# VOLTAGE_MEASURE_DC_V2.net
KiCad netlist of a schematic drawn in Altium Designer
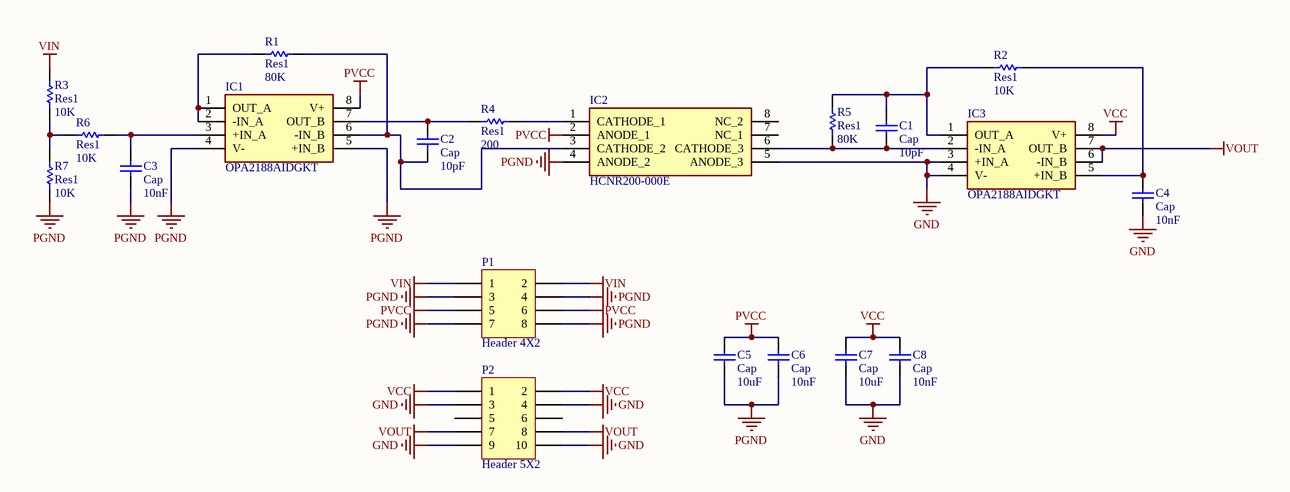
[diagram p0: VOLTAGE_MEASURE_DC_V2.SchDoc]

(export (version "E")
  (design (tool "Eeschema 10.0.6"))
  (components
    (comp (ref "C1")
      (value "Cap")
      (footprint "1608[0603]")
      (description "Capacitor")
      (fields (field (name "ALTIUM_VALUE") "10pF") (field (name "PUBLISHER") "Altium Limited"))
      (libsource (lib "Miscellaneous Devices") (part "Cap"))
    )
    (comp (ref "C2")
      (value "Cap")
      (footprint "1608[0603]")
      (description "Capacitor")
      (fields (field (name "ALTIUM_VALUE") "10pF") (field (name "PUBLISHER") "Altium Limited"))
      (libsource (lib "Miscellaneous Devices") (part "Cap"))
    )
    (comp (ref "C3")
      (value "Cap")
      (footprint "1608[0603]")
      (description "Capacitor")
      (fields (field (name "ALTIUM_VALUE") "10nF") (field (name "PUBLISHER") "Altium Limited"))
      (libsource (lib "Miscellaneous Devices") (part "Cap"))
    )
    (comp (ref "C4")
      (value "Cap")
      (footprint "1608[0603]")
      (description "Capacitor")
      (fields (field (name "ALTIUM_VALUE") "10nF") (field (name "PUBLISHER") "Altium Limited"))
      (libsource (lib "Miscellaneous Devices") (part "Cap"))
    )
    (comp (ref "C5")
      (value "Cap")
      (footprint "1608[0603]")
      (description "Capacitor")
      (fields (field (name "ALTIUM_VALUE") "10uF") (field (name "PUBLISHER") "Altium Limited"))
      (libsource (lib "Miscellaneous Devices") (part "Cap"))
    )
    (comp (ref "C6")
      (value "Cap")
      (footprint "1608[0603]")
      (description "Capacitor")
      (fields (field (name "ALTIUM_VALUE") "10nF") (field (name "PUBLISHER") "Altium Limited"))
      (libsource (lib "Miscellaneous Devices") (part "Cap"))
    )
    (comp (ref "C7")
      (value "Cap")
      (footprint "1608[0603]")
      (description "Capacitor")
      (fields (field (name "ALTIUM_VALUE") "10uF") (field (name "PUBLISHER") "Altium Limited"))
      (libsource (lib "Miscellaneous Devices") (part "Cap"))
    )
    (comp (ref "C8")
      (value "Cap")
      (footprint "1608[0603]")
      (description "Capacitor")
      (fields (field (name "ALTIUM_VALUE") "10nF") (field (name "PUBLISHER") "Altium Limited"))
      (libsource (lib "Miscellaneous Devices") (part "Cap"))
    )
    (comp (ref "IC1")
      (value "OPA2188AIDGKT")
      (footprint "SamacSys:SOP65P490X110-8N")
      (description "Integrated Circuit")
      (fields
        (field (name "MOUSER PART NUMBER") "595-OPA2188AIDGKT")
        (field (name "RS PART NUMBER") "8122561P")
      )
      (libsource (lib "*") (part "OPA2188AIDGKT"))
    )
    (comp (ref "IC2")
      (value "HCNR200-000E")
      (footprint "SamacSys:DIP1100W56P254L1115H510Q8N")
      (description "Integrated Circuit")
      (fields
        (field (name "MOUSER PART NUMBER") "630-HCNR200-000E")
        (field (name "RS PART NUMBER") "6961248P")
      )
      (libsource (lib "*") (part "HCNR200-000E"))
    )
    (comp (ref "IC3")
      (value "OPA2188AIDGKT")
      (footprint "SamacSys:SOP65P490X110-8N")
      (description "Integrated Circuit")
      (fields
        (field (name "MOUSER PART NUMBER") "595-OPA2188AIDGKT")
        (field (name "RS PART NUMBER") "8122561P")
      )
      (libsource (lib "*") (part "OPA2188AIDGKT"))
    )
    (comp (ref "P1")
      (value "Header 4X2")
      (footprint "HDR2X4")
      (description "Header, 4-Pin, Dual row")
      (fields (field (name "PUBLISHER") "Altium Limited"))
      (libsource (lib "Miscellaneous Connectors") (part "Header 4X2"))
    )
    (comp (ref "P2")
      (value "Header 5X2")
      (footprint "HDR2X5")
      (description "Header, 5-Pin, Dual row")
      (fields (field (name "PUBLISHER") "Altium Limited"))
      (libsource (lib "Miscellaneous Connectors") (part "Header 5X2"))
    )
    (comp (ref "R1")
      (value "Res1")
      (footprint "J1-0603")
      (description "Resistor")
      (fields (field (name "ALTIUM_VALUE") "80K") (field (name "PUBLISHER") "Altium Limited"))
      (libsource (lib "Miscellaneous Devices") (part "Res1"))
    )
    (comp (ref "R2")
      (value "Res1")
      (footprint "J1-0603")
      (description "Resistor")
      (fields (field (name "ALTIUM_VALUE") "10K") (field (name "PUBLISHER") "Altium Limited"))
      (libsource (lib "Miscellaneous Devices") (part "Res1"))
    )
    (comp (ref "R3")
      (value "Res1")
      (footprint "J1-0603")
      (description "Resistor")
      (fields (field (name "ALTIUM_VALUE") "10K") (field (name "PUBLISHER") "Altium Limited"))
      (libsource (lib "Miscellaneous Devices") (part "Res1"))
    )
    (comp (ref "R4")
      (value "Res1")
      (footprint "J1-0603")
      (description "Resistor")
      (fields (field (name "ALTIUM_VALUE") "200") (field (name "PUBLISHER") "Altium Limited"))
      (libsource (lib "Miscellaneous Devices") (part "Res1"))
    )
    (comp (ref "R5")
      (value "Res1")
      (footprint "J1-0603")
      (description "Resistor")
      (fields (field (name "ALTIUM_VALUE") "80K") (field (name "PUBLISHER") "Altium Limited"))
      (libsource (lib "Miscellaneous Devices") (part "Res1"))
    )
    (comp (ref "R6")
      (value "Res1")
      (footprint "J1-0603")
      (description "Resistor")
      (fields (field (name "ALTIUM_VALUE") "10K") (field (name "PUBLISHER") "Altium Limited"))
      (libsource (lib "Miscellaneous Devices") (part "Res1"))
    )
    (comp (ref "R7")
      (value "Res1")
      (footprint "J1-0603")
      (description "Resistor")
      (fields (field (name "ALTIUM_VALUE") "10K") (field (name "PUBLISHER") "Altium Limited"))
      (libsource (lib "Miscellaneous Devices") (part "Res1"))
    )
  )
  (nets
    (net (code "1") (name "GND") (class "Default")
      (node (ref "C4") (pin "1") (pinfunction "1_1") (pintype "passive"))
      (node (ref "C7") (pin "2") (pinfunction "2_2") (pintype "passive"))
      (node (ref "C8") (pin "2") (pinfunction "2_2") (pintype "passive"))
      (node (ref "IC2") (pin "5") (pinfunction "ANODE_3_5") (pintype "passive"))
      (node (ref "IC3") (pin "3") (pinfunction "+IN_A_3") (pintype "passive"))
      (node (ref "IC3") (pin "4") (pinfunction "V-_4") (pintype "passive"))
      (node (ref "P2") (pin "10") (pinfunction "10_10") (pintype "passive"))
      (node (ref "P2") (pin "3") (pinfunction "3_3") (pintype "passive"))
      (node (ref "P2") (pin "4") (pinfunction "4_4") (pintype "passive"))
      (node (ref "P2") (pin "9") (pinfunction "9_9") (pintype "passive"))
    )
    (net (code "2") (name "Net-(IC1-+IN_A)") (class "Default")
      (node (ref "C3") (pin "2") (pinfunction "2_2") (pintype "passive"))
      (node (ref "IC1") (pin "3") (pinfunction "+IN_A_3") (pintype "passive"))
      (node (ref "R6") (pin "1") (pinfunction "1_1") (pintype "passive"))
    )
    (net (code "3") (name "Net-(IC1--IN_A)") (class "Default")
      (node (ref "IC1") (pin "1") (pinfunction "OUT_A_1") (pintype "passive"))
      (node (ref "IC1") (pin "2") (pinfunction "-IN_A_2") (pintype "passive"))
      (node (ref "R1") (pin "2") (pinfunction "2_2") (pintype "passive"))
    )
    (net (code "4") (name "Net-(IC1--IN_B)") (class "Default")
      (node (ref "C2") (pin "2") (pinfunction "2_2") (pintype "passive"))
      (node (ref "IC1") (pin "6") (pinfunction "-IN_B_6") (pintype "passive"))
      (node (ref "IC2") (pin "3") (pinfunction "CATHODE_2_3") (pintype "passive"))
      (node (ref "R1") (pin "1") (pinfunction "1_1") (pintype "passive"))
    )
    (net (code "5") (name "Net-(IC1-OUT_B)") (class "Default")
      (node (ref "C2") (pin "1") (pinfunction "1_1") (pintype "passive"))
      (node (ref "IC1") (pin "7") (pinfunction "OUT_B_7") (pintype "passive"))
      (node (ref "R4") (pin "1") (pinfunction "1_1") (pintype "passive"))
    )
    (net (code "6") (name "Net-(IC2-CATHODE_1)") (class "Default")
      (node (ref "IC2") (pin "1") (pinfunction "CATHODE_1_1") (pintype "passive"))
      (node (ref "R4") (pin "2") (pinfunction "2_2") (pintype "passive"))
    )
    (net (code "7") (name "Net-(IC2-CATHODE_3)") (class "Default")
      (node (ref "C1") (pin "1") (pinfunction "1_1") (pintype "passive"))
      (node (ref "IC2") (pin "6") (pinfunction "CATHODE_3_6") (pintype "passive"))
      (node (ref "IC3") (pin "2") (pinfunction "-IN_A_2") (pintype "passive"))
      (node (ref "R5") (pin "2") (pinfunction "2_2") (pintype "passive"))
    )
    (net (code "8") (name "Net-(IC3-+IN_B)") (class "Default")
      (node (ref "C4") (pin "2") (pinfunction "2_2") (pintype "passive"))
      (node (ref "IC3") (pin "5") (pinfunction "+IN_B_5") (pintype "passive"))
      (node (ref "R2") (pin "2") (pinfunction "2_2") (pintype "passive"))
    )
    (net (code "9") (name "Net-(IC3-OUT_A)") (class "Default")
      (node (ref "C1") (pin "2") (pinfunction "2_2") (pintype "passive"))
      (node (ref "IC3") (pin "1") (pinfunction "OUT_A_1") (pintype "passive"))
      (node (ref "R2") (pin "1") (pinfunction "1_1") (pintype "passive"))
      (node (ref "R5") (pin "1") (pinfunction "1_1") (pintype "passive"))
    )
    (net (code "10") (name "Net-(R3-Pad1)") (class "Default")
      (node (ref "R3") (pin "1") (pinfunction "1_1") (pintype "passive"))
      (node (ref "R6") (pin "2") (pinfunction "2_2") (pintype "passive"))
      (node (ref "R7") (pin "2") (pinfunction "2_2") (pintype "passive"))
    )
    (net (code "11") (name "PGND") (class "Default")
      (node (ref "C3") (pin "1") (pinfunction "1_1") (pintype "passive"))
      (node (ref "C5") (pin "2") (pinfunction "2_2") (pintype "passive"))
      (node (ref "C6") (pin "2") (pinfunction "2_2") (pintype "passive"))
      (node (ref "IC1") (pin "4") (pinfunction "V-_4") (pintype "passive"))
      (node (ref "IC1") (pin "5") (pinfunction "+IN_B_5") (pintype "passive"))
      (node (ref "IC2") (pin "4") (pinfunction "ANODE_2_4") (pintype "passive"))
      (node (ref "P1") (pin "3") (pinfunction "3_3") (pintype "passive"))
      (node (ref "P1") (pin "4") (pinfunction "4_4") (pintype "passive"))
      (node (ref "P1") (pin "7") (pinfunction "7_7") (pintype "passive"))
      (node (ref "P1") (pin "8") (pinfunction "8_8") (pintype "passive"))
      (node (ref "R7") (pin "1") (pinfunction "1_1") (pintype "passive"))
    )
    (net (code "12") (name "PVCC") (class "Default")
      (node (ref "C5") (pin "1") (pinfunction "1_1") (pintype "passive"))
      (node (ref "C6") (pin "1") (pinfunction "1_1") (pintype "passive"))
      (node (ref "IC1") (pin "8") (pinfunction "V+_8") (pintype "passive"))
      (node (ref "IC2") (pin "2") (pinfunction "ANODE_1_2") (pintype "passive"))
      (node (ref "P1") (pin "5") (pinfunction "5_5") (pintype "passive"))
      (node (ref "P1") (pin "6") (pinfunction "6_6") (pintype "passive"))
    )
    (net (code "13") (name "VCC") (class "Default")
      (node (ref "C7") (pin "1") (pinfunction "1_1") (pintype "passive"))
      (node (ref "C8") (pin "1") (pinfunction "1_1") (pintype "passive"))
      (node (ref "IC3") (pin "8") (pinfunction "V+_8") (pintype "passive"))
      (node (ref "P2") (pin "1") (pinfunction "1_1") (pintype "passive"))
      (node (ref "P2") (pin "2") (pinfunction "2_2") (pintype "passive"))
    )
    (net (code "14") (name "VIN") (class "Default")
      (node (ref "P1") (pin "1") (pinfunction "1_1") (pintype "passive"))
      (node (ref "P1") (pin "2") (pinfunction "2_2") (pintype "passive"))
      (node (ref "R3") (pin "2") (pinfunction "2_2") (pintype "passive"))
    )
    (net (code "15") (name "VOUT") (class "Default")
      (node (ref "IC3") (pin "6") (pinfunction "-IN_B_6") (pintype "passive"))
      (node (ref "IC3") (pin "7") (pinfunction "OUT_B_7") (pintype "passive"))
      (node (ref "P2") (pin "7") (pinfunction "7_7") (pintype "passive"))
      (node (ref "P2") (pin "8") (pinfunction "8_8") (pintype "passive"))
    )
    (net (code "16") (name "unconnected-(IC2-NC_1-Pad7)") (class "Default")
      (node (ref "IC2") (pin "7") (pinfunction "NC_1_7") (pintype "passive"))
    )
    (net (code "17") (name "unconnected-(IC2-NC_2-Pad8)") (class "Default")
      (node (ref "IC2") (pin "8") (pinfunction "NC_2_8") (pintype "passive"))
    )
    (net (code "18") (name "unconnected-(P2-Pad5)") (class "Default")
      (node (ref "P2") (pin "5") (pinfunction "5_5") (pintype "passive"))
    )
    (net (code "19") (name "unconnected-(P2-Pad6)") (class "Default")
      (node (ref "P2") (pin "6") (pinfunction "6_6") (pintype "passive"))
    )
  )
)
